# Sensor-board.net
KiCad netlist of a schematic drawn in EAGLE
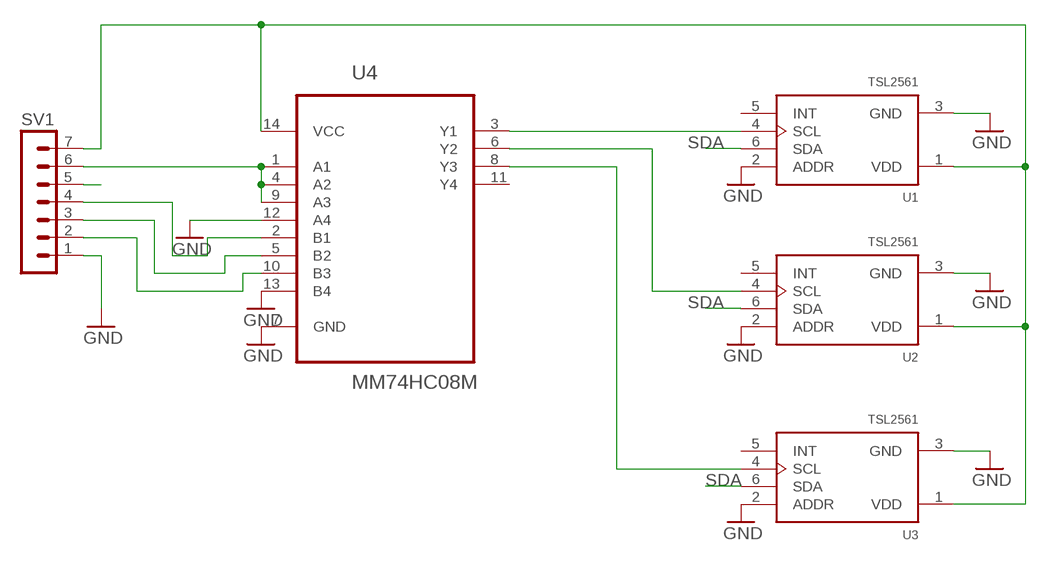
[diagram p0: schematic, sheet 1]

(export (version "E")
  (design (tool "Eeschema 10.0.6"))
  (components
    (comp (ref "SV1")
      (value "MA07-1")
      (footprint "eagle-import:MA07-1")
      (libsource (lib "eagle-import") (part "MA07-1"))
    )
    (comp (ref "U1")
      (value "TSL2561")
      (footprint "eagle-import:TMB-6")
      (libsource (lib "eagle-import") (part "TSL2561"))
    )
    (comp (ref "U2")
      (value "TSL2561")
      (footprint "eagle-import:TMB-6")
      (libsource (lib "eagle-import") (part "TSL2561"))
    )
    (comp (ref "U3")
      (value "TSL2561")
      (footprint "eagle-import:TMB-6")
      (libsource (lib "eagle-import") (part "TSL2561"))
    )
    (comp (ref "U4")
      (value "MM74HC08M")
      (footprint "eagle-import:SOIC127P600X175-14N")
      (libsource (lib "eagle-import") (part "MM74HC08M"))
    )
  )
  (nets
    (net (code "1") (name "/SDA") (class "Default")
      (node (ref "SV1") (pin "5") (pinfunction "5_5") (pintype "passive"))
      (node (ref "U1") (pin "6") (pinfunction "SDA_6") (pintype "bidirectional"))
      (node (ref "U2") (pin "6") (pinfunction "SDA_6") (pintype "bidirectional"))
      (node (ref "U3") (pin "6") (pinfunction "SDA_6") (pintype "bidirectional"))
    )
    (net (code "2") (name "GND") (class "Default")
      (node (ref "SV1") (pin "1") (pinfunction "1_1") (pintype "passive"))
      (node (ref "U1") (pin "2") (pinfunction "ADDR_2") (pintype "input"))
      (node (ref "U1") (pin "3") (pinfunction "GND_3") (pintype "power_in"))
      (node (ref "U2") (pin "2") (pinfunction "ADDR_2") (pintype "input"))
      (node (ref "U2") (pin "3") (pinfunction "GND_3") (pintype "power_in"))
      (node (ref "U3") (pin "2") (pinfunction "ADDR_2") (pintype "input"))
      (node (ref "U3") (pin "3") (pinfunction "GND_3") (pintype "power_in"))
      (node (ref "U4") (pin "12") (pinfunction "A4_12") (pintype "input"))
      (node (ref "U4") (pin "13") (pinfunction "B4_13") (pintype "input"))
      (node (ref "U4") (pin "7") (pinfunction "GND_7") (pintype "passive"))
    )
    (net (code "3") (name "Net-(U1-SCL)") (class "Default")
      (node (ref "U1") (pin "4") (pinfunction "SCL_4") (pintype "input"))
      (node (ref "U4") (pin "3") (pinfunction "Y1_3") (pintype "output"))
    )
    (net (code "4") (name "Net-(U1-VDD)") (class "Default")
      (node (ref "SV1") (pin "7") (pinfunction "7_7") (pintype "passive"))
      (node (ref "U1") (pin "1") (pinfunction "VDD_1") (pintype "power_in"))
      (node (ref "U2") (pin "1") (pinfunction "VDD_1") (pintype "power_in"))
      (node (ref "U3") (pin "1") (pinfunction "VDD_1") (pintype "power_in"))
      (node (ref "U4") (pin "14") (pinfunction "VCC_14") (pintype "power_in"))
    )
    (net (code "5") (name "Net-(U2-SCL)") (class "Default")
      (node (ref "U2") (pin "4") (pinfunction "SCL_4") (pintype "input"))
      (node (ref "U4") (pin "6") (pinfunction "Y2_6") (pintype "output"))
    )
    (net (code "6") (name "Net-(U3-SCL)") (class "Default")
      (node (ref "U3") (pin "4") (pinfunction "SCL_4") (pintype "input"))
      (node (ref "U4") (pin "8") (pinfunction "Y3_8") (pintype "output"))
    )
    (net (code "7") (name "Net-(U4-A1)") (class "Default")
      (node (ref "SV1") (pin "6") (pinfunction "6_6") (pintype "passive"))
      (node (ref "U4") (pin "1") (pinfunction "A1_1") (pintype "input"))
      (node (ref "U4") (pin "4") (pinfunction "A2_4") (pintype "input"))
      (node (ref "U4") (pin "9") (pinfunction "A3_9") (pintype "input"))
    )
    (net (code "8") (name "Net-(U4-B1)") (class "Default")
      (node (ref "SV1") (pin "4") (pinfunction "4_4") (pintype "passive"))
      (node (ref "U4") (pin "2") (pinfunction "B1_2") (pintype "input"))
    )
    (net (code "9") (name "Net-(U4-B2)") (class "Default")
      (node (ref "SV1") (pin "3") (pinfunction "3_3") (pintype "passive"))
      (node (ref "U4") (pin "5") (pinfunction "B2_5") (pintype "input"))
    )
    (net (code "10") (name "Net-(U4-B3)") (class "Default")
      (node (ref "SV1") (pin "2") (pinfunction "2_2") (pintype "passive"))
      (node (ref "U4") (pin "10") (pinfunction "B3_10") (pintype "input"))
    )
    (net (code "11") (name "unconnected-(U1-INT-Pad5)") (class "Default")
      (node (ref "U1") (pin "5") (pinfunction "INT_5") (pintype "output"))
    )
    (net (code "12") (name "unconnected-(U2-INT-Pad5)") (class "Default")
      (node (ref "U2") (pin "5") (pinfunction "INT_5") (pintype "output"))
    )
    (net (code "13") (name "unconnected-(U3-INT-Pad5)") (class "Default")
      (node (ref "U3") (pin "5") (pinfunction "INT_5") (pintype "output"))
    )
    (net (code "14") (name "unconnected-(U4-Y4-Pad11)") (class "Default")
      (node (ref "U4") (pin "11") (pinfunction "Y4_11") (pintype "output"))
    )
  )
)
